# Due_VGA_Shield.net
KiCad netlist of a schematic drawn in EAGLE
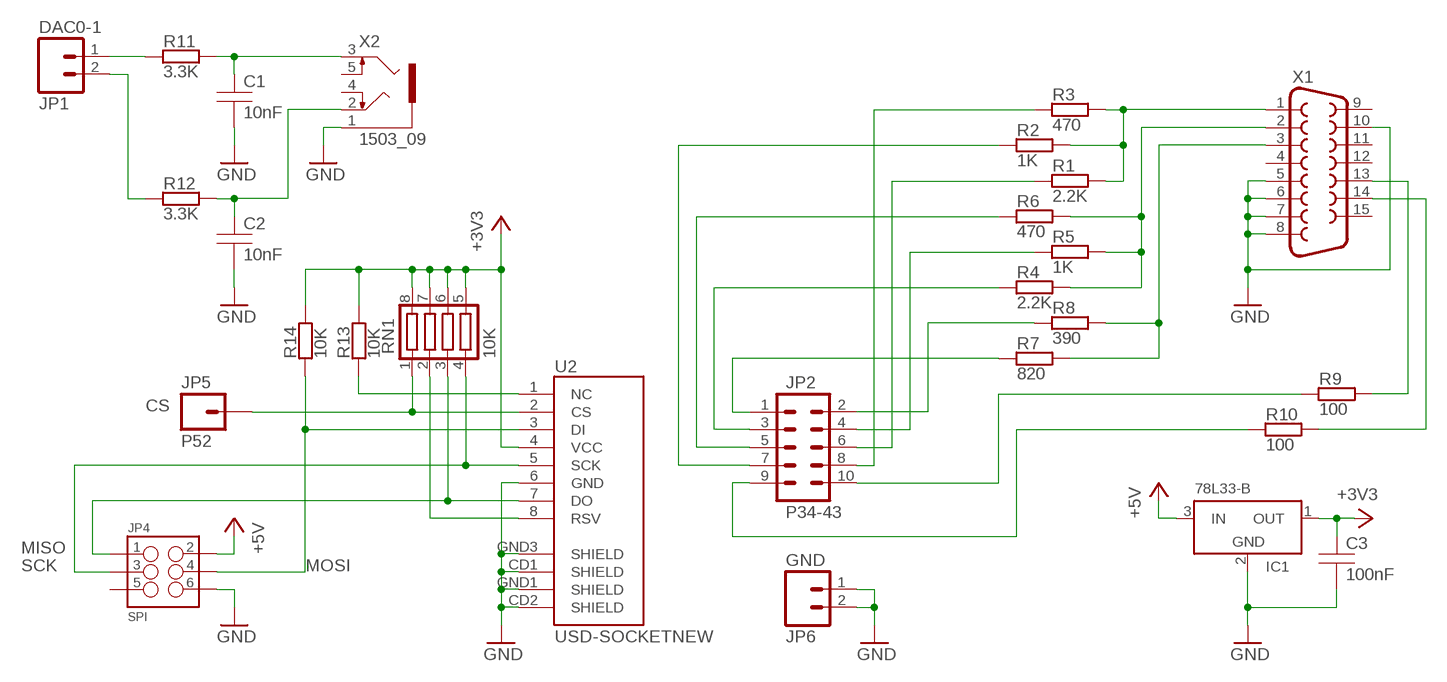
[diagram p0: schematic, sheet 1]

(export (version "E")
  (design (tool "Eeschema 10.0.6"))
  (components
    (comp (ref "C1")
      (value "10nF")
      (footprint "eagle-import:SMD-2012")
      (libsource (lib "eagle-import") (part "CAPACITOR_CERAM-SMD-2012"))
    )
    (comp (ref "C2")
      (value "10nF")
      (footprint "eagle-import:SMD-2012")
      (libsource (lib "eagle-import") (part "CAPACITOR_CERAM-SMD-2012"))
    )
    (comp (ref "C3")
      (value "100nF")
      (footprint "eagle-import:SMD-2012")
      (libsource (lib "eagle-import") (part "CAPACITOR_CERAM-SMD-2012"))
    )
    (comp (ref "IC1")
      (value "78L33-B")
      (footprint "eagle-import:TO-92_M")
      (libsource (lib "eagle-import") (part "78L33-B"))
    )
    (comp (ref "JP1")
      (value "DAC0-1")
      (footprint "eagle-import:1X02")
      (libsource (lib "eagle-import") (part "M02PTH"))
    )
    (comp (ref "JP2")
      (value "P34-43")
      (footprint "eagle-import:AVR_ICSP")
      (libsource (lib "eagle-import") (part "M05X2PTH"))
    )
    (comp (ref "JP4")
      (value "SPI")
      (footprint "eagle-import:2X3")
      (libsource (lib "eagle-import") (part "M03X22X3_SILK_SM"))
    )
    (comp (ref "JP5")
      (value "P52")
      (footprint "eagle-import:1X01")
      (libsource (lib "eagle-import") (part "M01PTH"))
    )
    (comp (ref "JP6")
      (value "GND")
      (footprint "eagle-import:1X02")
      (libsource (lib "eagle-import") (part "M02PTH"))
    )
    (comp (ref "R1")
      (value "2.2K")
      (footprint "eagle-import:SMD-2012")
      (libsource (lib "eagle-import") (part "RESISTENCIA-SMD-2012"))
    )
    (comp (ref "R2")
      (value "1K")
      (footprint "eagle-import:SMD-2012")
      (libsource (lib "eagle-import") (part "RESISTENCIA-SMD-2012"))
    )
    (comp (ref "R3")
      (value "470")
      (footprint "eagle-import:SMD-2012")
      (libsource (lib "eagle-import") (part "RESISTENCIA-SMD-2012"))
    )
    (comp (ref "R4")
      (value "2.2K")
      (footprint "eagle-import:SMD-2012")
      (libsource (lib "eagle-import") (part "RESISTENCIA-SMD-2012"))
    )
    (comp (ref "R5")
      (value "1K")
      (footprint "eagle-import:SMD-2012")
      (libsource (lib "eagle-import") (part "RESISTENCIA-SMD-2012"))
    )
    (comp (ref "R6")
      (value "470")
      (footprint "eagle-import:SMD-2012")
      (libsource (lib "eagle-import") (part "RESISTENCIA-SMD-2012"))
    )
    (comp (ref "R7")
      (value "820")
      (footprint "eagle-import:SMD-2012")
      (libsource (lib "eagle-import") (part "RESISTENCIA-SMD-2012"))
    )
    (comp (ref "R8")
      (value "390")
      (footprint "eagle-import:SMD-2012")
      (libsource (lib "eagle-import") (part "RESISTENCIA-SMD-2012"))
    )
    (comp (ref "R9")
      (value "100")
      (footprint "eagle-import:SMD-2012")
      (libsource (lib "eagle-import") (part "RESISTENCIA-SMD-2012"))
    )
    (comp (ref "R10")
      (value "100")
      (footprint "eagle-import:SMD-2012")
      (libsource (lib "eagle-import") (part "RESISTENCIA-SMD-2012"))
    )
    (comp (ref "R11")
      (value "3.3K")
      (footprint "eagle-import:SMD-2012")
      (libsource (lib "eagle-import") (part "RESISTENCIA-SMD-2012"))
    )
    (comp (ref "R12")
      (value "3.3K")
      (footprint "eagle-import:SMD-2012")
      (libsource (lib "eagle-import") (part "RESISTENCIA-SMD-2012"))
    )
    (comp (ref "R13")
      (value "10K")
      (footprint "eagle-import:SMD-2012")
      (libsource (lib "eagle-import") (part "RESISTENCIA-SMD-2012"))
    )
    (comp (ref "R14")
      (value "10K")
      (footprint "eagle-import:SMD-2012")
      (libsource (lib "eagle-import") (part "RESISTENCIA-SMD-2012"))
    )
    (comp (ref "RN1")
      (value "10K")
      (footprint "eagle-import:CTS742C083")
      (libsource (lib "eagle-import") (part "CTS742C083"))
    )
    (comp (ref "U2")
      (value "USD-SOCKETNEW")
      (footprint "eagle-import:MICRO-SD-SOCKET-PP")
      (libsource (lib "eagle-import") (part "USD-SOCKETNEW"))
    )
    (comp (ref "X1")
      (value "F15HDH")
      (footprint "eagle-import:HDF15H")
      (libsource (lib "eagle-import") (part "F15HDH"))
    )
    (comp (ref "X2")
      (value "1503_09")
      (footprint "eagle-import:1503_09")
      (libsource (lib "eagle-import") (part "1503_09"))
    )
  )
  (nets
    (net (code "1") (name "+3V3") (class "Default")
      (node (ref "C3") (pin "P$1") (pinfunction "1_P$1") (pintype "bidirectional"))
      (node (ref "IC1") (pin "1") (pinfunction "OUT_1") (pintype "bidirectional"))
      (node (ref "R13") (pin "P$1") (pinfunction "P$1_P$1") (pintype "bidirectional"))
      (node (ref "R14") (pin "P$1") (pinfunction "P$1_P$1") (pintype "bidirectional"))
      (node (ref "RN1") (pin "5") (pinfunction "5_5") (pintype "passive"))
      (node (ref "RN1") (pin "6") (pinfunction "6_6") (pintype "passive"))
      (node (ref "RN1") (pin "7") (pinfunction "7_7") (pintype "passive"))
      (node (ref "RN1") (pin "8") (pinfunction "8_8") (pintype "passive"))
      (node (ref "U2") (pin "4") (pinfunction "VCC_4") (pintype "bidirectional"))
    )
    (net (code "2") (name "+5V") (class "Default")
      (node (ref "IC1") (pin "3") (pinfunction "IN_3") (pintype "bidirectional"))
      (node (ref "JP4") (pin "2") (pinfunction "2_2") (pintype "bidirectional"))
    )
    (net (code "3") (name "/CS") (class "Default")
      (node (ref "JP5") (pin "1") (pinfunction "1_1") (pintype "passive"))
      (node (ref "RN1") (pin "1") (pinfunction "1_1") (pintype "passive"))
      (node (ref "U2") (pin "2") (pinfunction "CS_2") (pintype "bidirectional"))
    )
    (net (code "4") (name "/MISO") (class "Default")
      (node (ref "JP4") (pin "1") (pinfunction "1_1") (pintype "bidirectional"))
      (node (ref "RN1") (pin "3") (pinfunction "3_3") (pintype "passive"))
      (node (ref "U2") (pin "7") (pinfunction "DO_7") (pintype "bidirectional"))
    )
    (net (code "5") (name "/MOSI") (class "Default")
      (node (ref "JP4") (pin "4") (pinfunction "4_4") (pintype "bidirectional"))
      (node (ref "R14") (pin "P$2") (pinfunction "P$2_P$2") (pintype "bidirectional"))
      (node (ref "U2") (pin "3") (pinfunction "DI_3") (pintype "bidirectional"))
    )
    (net (code "6") (name "/SCK") (class "Default")
      (node (ref "JP4") (pin "3") (pinfunction "3_3") (pintype "bidirectional"))
      (node (ref "RN1") (pin "4") (pinfunction "4_4") (pintype "passive"))
      (node (ref "U2") (pin "5") (pinfunction "SCK_5") (pintype "bidirectional"))
    )
    (net (code "7") (name "GND") (class "Default")
      (node (ref "C1") (pin "P$2") (pinfunction "2_P$2") (pintype "bidirectional"))
      (node (ref "C2") (pin "P$2") (pinfunction "2_P$2") (pintype "bidirectional"))
      (node (ref "C3") (pin "P$2") (pinfunction "2_P$2") (pintype "bidirectional"))
      (node (ref "IC1") (pin "2") (pinfunction "GND_2") (pintype "bidirectional"))
      (node (ref "JP4") (pin "6") (pinfunction "6_6") (pintype "bidirectional"))
      (node (ref "JP6") (pin "1") (pinfunction "1_1") (pintype "passive"))
      (node (ref "JP6") (pin "2") (pinfunction "2_2") (pintype "passive"))
      (node (ref "U2") (pin "6") (pinfunction "GND_6") (pintype "bidirectional"))
      (node (ref "U2") (pin "CD1") (pinfunction "SHIELD_CD1") (pintype "bidirectional"))
      (node (ref "U2") (pin "CD2") (pinfunction "SHIELD_CD2") (pintype "bidirectional"))
      (node (ref "U2") (pin "GND1") (pinfunction "SHIELD_GND1") (pintype "bidirectional"))
      (node (ref "U2") (pin "GND3") (pinfunction "SHIELD_GND3") (pintype "bidirectional"))
      (node (ref "X1") (pin "10") (pinfunction "10_10") (pintype "passive"))
      (node (ref "X1") (pin "5") (pinfunction "5_5") (pintype "passive"))
      (node (ref "X1") (pin "6") (pinfunction "6_6") (pintype "passive"))
      (node (ref "X1") (pin "7") (pinfunction "7_7") (pintype "passive"))
      (node (ref "X1") (pin "8") (pinfunction "8_8") (pintype "passive"))
      (node (ref "X2") (pin "1") (pinfunction "1_1") (pintype "passive"))
    )
    (net (code "8") (name "Net-(C1-1)") (class "Default")
      (node (ref "C1") (pin "P$1") (pinfunction "1_P$1") (pintype "bidirectional"))
      (node (ref "R11") (pin "P$1") (pinfunction "P$1_P$1") (pintype "bidirectional"))
      (node (ref "X2") (pin "3") (pinfunction "3_3") (pintype "passive"))
    )
    (net (code "9") (name "Net-(C2-1)") (class "Default")
      (node (ref "C2") (pin "P$1") (pinfunction "1_P$1") (pintype "bidirectional"))
      (node (ref "R12") (pin "P$1") (pinfunction "P$1_P$1") (pintype "bidirectional"))
      (node (ref "X2") (pin "2") (pinfunction "2_2") (pintype "passive"))
    )
    (net (code "10") (name "Net-(JP1-Pad1)") (class "Default")
      (node (ref "JP1") (pin "1") (pinfunction "1_1") (pintype "passive"))
      (node (ref "R11") (pin "P$2") (pinfunction "P$2_P$2") (pintype "bidirectional"))
    )
    (net (code "11") (name "Net-(JP1-Pad2)") (class "Default")
      (node (ref "JP1") (pin "2") (pinfunction "2_2") (pintype "passive"))
      (node (ref "R12") (pin "P$2") (pinfunction "P$2_P$2") (pintype "bidirectional"))
    )
    (net (code "12") (name "Net-(JP2-Pad1)") (class "Default")
      (node (ref "JP2") (pin "1") (pinfunction "1_1") (pintype "passive"))
      (node (ref "R7") (pin "P$2") (pinfunction "P$2_P$2") (pintype "bidirectional"))
    )
    (net (code "13") (name "Net-(JP2-Pad2)") (class "Default")
      (node (ref "JP2") (pin "2") (pinfunction "2_2") (pintype "passive"))
      (node (ref "R8") (pin "P$2") (pinfunction "P$2_P$2") (pintype "bidirectional"))
    )
    (net (code "14") (name "Net-(JP2-Pad3)") (class "Default")
      (node (ref "JP2") (pin "3") (pinfunction "3_3") (pintype "passive"))
      (node (ref "R4") (pin "P$2") (pinfunction "P$2_P$2") (pintype "bidirectional"))
    )
    (net (code "15") (name "Net-(JP2-Pad4)") (class "Default")
      (node (ref "JP2") (pin "4") (pinfunction "4_4") (pintype "passive"))
      (node (ref "R5") (pin "P$2") (pinfunction "P$2_P$2") (pintype "bidirectional"))
    )
    (net (code "16") (name "Net-(JP2-Pad5)") (class "Default")
      (node (ref "JP2") (pin "5") (pinfunction "5_5") (pintype "passive"))
      (node (ref "R6") (pin "P$2") (pinfunction "P$2_P$2") (pintype "bidirectional"))
    )
    (net (code "17") (name "Net-(JP2-Pad6)") (class "Default")
      (node (ref "JP2") (pin "6") (pinfunction "6_6") (pintype "passive"))
      (node (ref "R1") (pin "P$2") (pinfunction "P$2_P$2") (pintype "bidirectional"))
    )
    (net (code "18") (name "Net-(JP2-Pad7)") (class "Default")
      (node (ref "JP2") (pin "7") (pinfunction "7_7") (pintype "passive"))
      (node (ref "R2") (pin "P$2") (pinfunction "P$2_P$2") (pintype "bidirectional"))
    )
    (net (code "19") (name "Net-(JP2-Pad8)") (class "Default")
      (node (ref "JP2") (pin "8") (pinfunction "8_8") (pintype "passive"))
      (node (ref "R3") (pin "P$2") (pinfunction "P$2_P$2") (pintype "bidirectional"))
    )
    (net (code "20") (name "Net-(JP2-Pad9)") (class "Default")
      (node (ref "JP2") (pin "9") (pinfunction "9_9") (pintype "passive"))
      (node (ref "R10") (pin "P$2") (pinfunction "P$2_P$2") (pintype "bidirectional"))
    )
    (net (code "21") (name "Net-(JP2-Pad10)") (class "Default")
      (node (ref "JP2") (pin "10") (pinfunction "10_10") (pintype "passive"))
      (node (ref "R9") (pin "P$2") (pinfunction "P$2_P$2") (pintype "bidirectional"))
    )
    (net (code "22") (name "Net-(R1-PadP$1)") (class "Default")
      (node (ref "R1") (pin "P$1") (pinfunction "P$1_P$1") (pintype "bidirectional"))
      (node (ref "R2") (pin "P$1") (pinfunction "P$1_P$1") (pintype "bidirectional"))
      (node (ref "R3") (pin "P$1") (pinfunction "P$1_P$1") (pintype "bidirectional"))
      (node (ref "X1") (pin "1") (pinfunction "1_1") (pintype "passive"))
    )
    (net (code "23") (name "Net-(R4-PadP$1)") (class "Default")
      (node (ref "R4") (pin "P$1") (pinfunction "P$1_P$1") (pintype "bidirectional"))
      (node (ref "R5") (pin "P$1") (pinfunction "P$1_P$1") (pintype "bidirectional"))
      (node (ref "R6") (pin "P$1") (pinfunction "P$1_P$1") (pintype "bidirectional"))
      (node (ref "X1") (pin "2") (pinfunction "2_2") (pintype "passive"))
    )
    (net (code "24") (name "Net-(R7-PadP$1)") (class "Default")
      (node (ref "R7") (pin "P$1") (pinfunction "P$1_P$1") (pintype "bidirectional"))
      (node (ref "R8") (pin "P$1") (pinfunction "P$1_P$1") (pintype "bidirectional"))
      (node (ref "X1") (pin "3") (pinfunction "3_3") (pintype "passive"))
    )
    (net (code "25") (name "Net-(R9-PadP$1)") (class "Default")
      (node (ref "R9") (pin "P$1") (pinfunction "P$1_P$1") (pintype "bidirectional"))
      (node (ref "X1") (pin "13") (pinfunction "13_13") (pintype "passive"))
    )
    (net (code "26") (name "Net-(R10-PadP$1)") (class "Default")
      (node (ref "R10") (pin "P$1") (pinfunction "P$1_P$1") (pintype "bidirectional"))
      (node (ref "X1") (pin "14") (pinfunction "14_14") (pintype "passive"))
    )
    (net (code "27") (name "Net-(U2-NC)") (class "Default")
      (node (ref "R13") (pin "P$2") (pinfunction "P$2_P$2") (pintype "bidirectional"))
      (node (ref "U2") (pin "1") (pinfunction "NC_1") (pintype "bidirectional"))
    )
    (net (code "28") (name "Net-(U2-RSV)") (class "Default")
      (node (ref "RN1") (pin "2") (pinfunction "2_2") (pintype "passive"))
      (node (ref "U2") (pin "8") (pinfunction "RSV_8") (pintype "bidirectional"))
    )
    (net (code "29") (name "unconnected-(JP4-Pad5)") (class "Default")
      (node (ref "JP4") (pin "5") (pinfunction "5_5") (pintype "bidirectional"))
    )
    (net (code "30") (name "unconnected-(X1-Pad4)") (class "Default")
      (node (ref "X1") (pin "4") (pinfunction "4_4") (pintype "passive"))
    )
    (net (code "31") (name "unconnected-(X1-Pad9)") (class "Default")
      (node (ref "X1") (pin "9") (pinfunction "9_9") (pintype "passive"))
    )
    (net (code "32") (name "unconnected-(X1-Pad11)") (class "Default")
      (node (ref "X1") (pin "11") (pinfunction "11_11") (pintype "passive"))
    )
    (net (code "33") (name "unconnected-(X1-Pad12)") (class "Default")
      (node (ref "X1") (pin "12") (pinfunction "12_12") (pintype "passive"))
    )
    (net (code "34") (name "unconnected-(X1-Pad15)") (class "Default")
      (node (ref "X1") (pin "15") (pinfunction "15_15") (pintype "passive"))
    )
    (net (code "35") (name "unconnected-(X2-Pad4)") (class "Default")
      (node (ref "X2") (pin "4") (pinfunction "4_4") (pintype "passive"))
    )
    (net (code "36") (name "unconnected-(X2-Pad5)") (class "Default")
      (node (ref "X2") (pin "5") (pinfunction "5_5") (pintype "passive"))
    )
  )
)
